# Board_Scale.net
KiCad netlist of a schematic drawn in Altium Designer
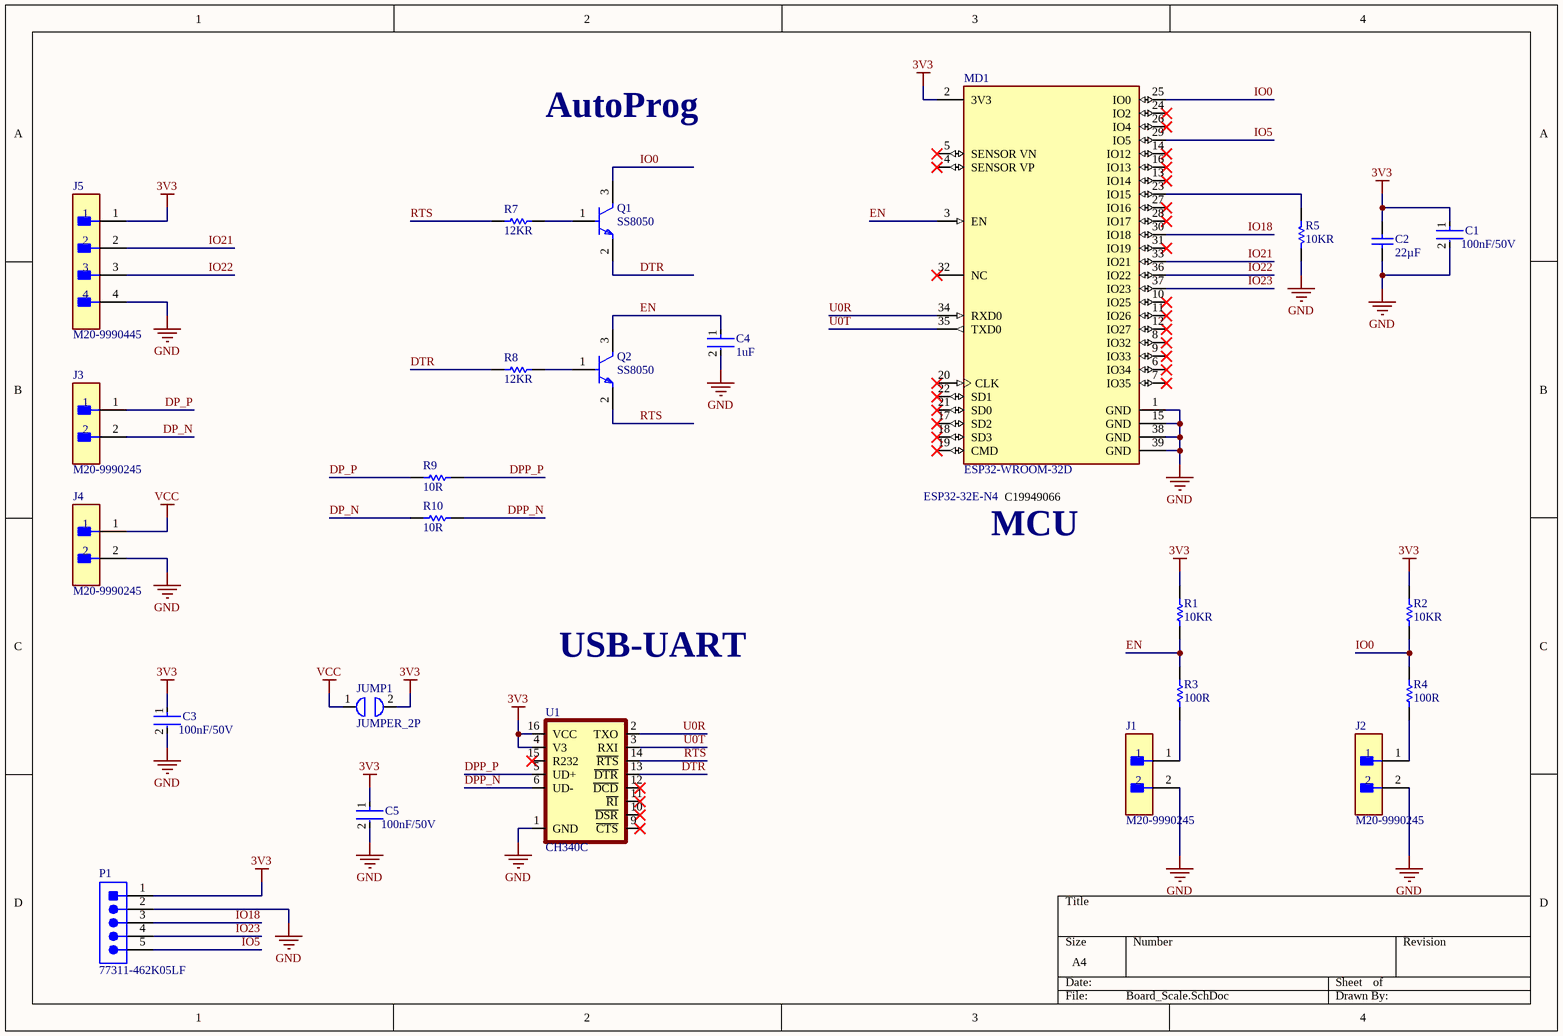
[diagram p0: Board_Scale.SchDoc]

(export (version "E")
  (design (tool "Eeschema 10.0.6"))
  (components
    (comp (ref "C1")
      (value "100nF/50V")
      (footprint "FP-CC0603-DA-MFG")
      (description "CAP CER 0.1UF 50V X7R 0603")
      (fields (field (name "MANUFACTURER") "YAGEO") (field (name "VOLTAGE") "50 V"))
      (libsource (lib "Altium Content Vault") (part "11868f565c42a9108669ba33697ecf6"))
    )
    (comp (ref "C2")
      (value "CL21A226MAQNNNE")
      (footprint "CAPC2013X140X45LL15T25")
      (description "Multi-layer Ceramic Capacitor, 22 uF, -55 to 85 degC, 2-Pin SMD (0805), RoHS, Tape and Reel")
      (fields
        (field (name "CAPACITANCE") "22µF")
        (field (name "MANUFACTURER") "Samsung Electro-Mechanics")
        (field (name "TOLERANCE") "±20%")
      )
      (libsource (lib "Altium Content Vault") (part "CAP-NP-2"))
    )
    (comp (ref "C3")
      (value "100nF/50V")
      (footprint "FP-CC0603-DA-MFG")
      (description "CAP CER 0.1UF 50V X7R 0603")
      (fields (field (name "MANUFACTURER") "YAGEO") (field (name "VOLTAGE") "50 V"))
      (libsource (lib "Altium Content Vault") (part "11868f565c42a9108669ba33697ecf6"))
    )
    (comp (ref "C4")
      (value "1uF")
      (footprint "FP-CL10-IPC_A")
      (description "Cap Ceramic 1uF 16V X5R ±10% Pad SMD 0603 +85°C T/R")
      (fields (field (name "TOLERANCE") "10%") (field (name "VOLTAGE") "16V"))
      (libsource (lib "Altium Content Vault") (part "b4654b650e69147ec39a6b967a45e02"))
    )
    (comp (ref "C5")
      (value "100nF/50V")
      (footprint "FP-CC0603-DA-MFG")
      (description "CAP CER 0.1UF 50V X7R 0603")
      (fields (field (name "MANUFACTURER") "YAGEO") (field (name "VOLTAGE") "50 V"))
      (libsource (lib "Altium Content Vault") (part "11868f565c42a9108669ba33697ecf6"))
    )
    (comp (ref "J1")
      (value "M20-9990245")
      (footprint "FP-M20-9990245-MFG")
      (description "CONN HEADER VERT 2POS 2.54MM")
      (fields (field (name "VOLTAGE") "50V"))
      (libsource (lib "Altium Content Vault") (part "3bc925449376181038e59eaffc5286c"))
    )
    (comp (ref "J2")
      (value "M20-9990245")
      (footprint "FP-M20-9990245-MFG")
      (description "CONN HEADER VERT 2POS 2.54MM")
      (fields (field (name "VOLTAGE") "50V"))
      (libsource (lib "Altium Content Vault") (part "3bc925449376181038e59eaffc5286c"))
    )
    (comp (ref "J3")
      (value "M20-9990245")
      (footprint "FP-M20-9990245-MFG")
      (description "CONN HEADER VERT 2POS 2.54MM")
      (fields (field (name "VOLTAGE") "50V"))
      (libsource (lib "Altium Content Vault") (part "3bc925449376181038e59eaffc5286c"))
    )
    (comp (ref "J4")
      (value "M20-9990245")
      (footprint "FP-M20-9990245-MFG")
      (description "CONN HEADER VERT 2POS 2.54MM")
      (fields (field (name "VOLTAGE") "50V"))
      (libsource (lib "Altium Content Vault") (part "3bc925449376181038e59eaffc5286c"))
    )
    (comp (ref "J5")
      (value "M20-9990445")
      (footprint "FP-M20-9990445-MFG")
      (description "M20-9990445 Conn Unshrouded Header HDR 4 POS 2.54mm Solder ST Thru-Hole Bulk/Loose")
      (libsource (lib "Altium Content Vault") (part "299a8cea1bdcbc3624fe62c390fa72c"))
    )
    (comp (ref "JUMP1")
      (value "JUMPER_2P")
      (footprint "JUMPER_2P")
      (libsource (lib "JUMPER_2P") (part "JUMPER_2P"))
    )
    (comp (ref "MD1")
      (value "ESP32-WROOM-32D")
      (footprint "FP-ESP32-WROOM-32D-MFG")
      (description "WIFI MODULE 32MBITS SPI FLASH")
      (fields
        (field (name "OCTOPART") "https://octopart.com/esp32-wroom-32d-espressif+systems-91040050")
        (field (name "MANUFACTURER") "Espressif Systems")
      )
      (libsource (lib "Altium Content Vault") (part "a031a76f8c27026a7a7f4657ff233a3"))
    )
    (comp (ref "P1")
      (value "77311-462K05LF")
      (footprint "FCI-77311-5_V")
      (libsource (lib "Altium Content Vault") (part "CN-1P-M-R5"))
    )
    (comp (ref "Q1")
      (value "SS8050")
      (footprint "FP-SS8050-G-MFG")
      (description "NPN TRANSISTOR 1.5A 40V SOT-23 R")
      (libsource (lib "Altium Content Vault") (part "2a1388f82443b098dcd57d24ac7632d"))
    )
    (comp (ref "Q2")
      (value "SS8050")
      (footprint "FP-SS8050-G-MFG")
      (description "NPN TRANSISTOR 1.5A 40V SOT-23 R")
      (libsource (lib "Altium Content Vault") (part "2a1388f82443b098dcd57d24ac7632d"))
    )
    (comp (ref "R1")
      (value "10KR")
      (footprint "RESC1609X55X30LL15T15")
      (description "Chip Resistor, 10 KOhm, +/- 1%, 0.1 W, -55 to 155 degC, 0603 (1608 Metric), RoHS, Tape and Reel")
      (fields (field (name "TOLERANCE") "1%") (field (name "MANUFACTURER") "Panasonic"))
      (libsource (lib "Altium Content Vault") (part "RES-2"))
    )
    (comp (ref "R2")
      (value "10KR")
      (footprint "RESC1609X55X30LL15T15")
      (description "Chip Resistor, 10 KOhm, +/- 1%, 0.1 W, -55 to 155 degC, 0603 (1608 Metric), RoHS, Tape and Reel")
      (fields (field (name "TOLERANCE") "1%") (field (name "MANUFACTURER") "Panasonic"))
      (libsource (lib "Altium Content Vault") (part "RES-2"))
    )
    (comp (ref "R3")
      (value "100R")
      (footprint "RESC1608X55X30LL15T15")
      (fields (field (name "MANUFACTURER") "Panasonic") (field (name "PART NUMBER") "ERJ-3EKF1000V"))
      (libsource (lib "Altium Content Vault") (part "RES"))
    )
    (comp (ref "R4")
      (value "100R")
      (footprint "RESC1608X55X30LL15T15")
      (fields (field (name "MANUFACTURER") "Panasonic") (field (name "PART NUMBER") "ERJ-3EKF1000V"))
      (libsource (lib "Altium Content Vault") (part "RES"))
    )
    (comp (ref "R5")
      (value "10KR")
      (footprint "RESC1609X55X30LL15T15")
      (description "Chip Resistor, 10 KOhm, +/- 1%, 0.1 W, -55 to 155 degC, 0603 (1608 Metric), RoHS, Tape and Reel")
      (fields (field (name "TOLERANCE") "1%") (field (name "MANUFACTURER") "Panasonic"))
      (libsource (lib "Altium Content Vault") (part "RES-2"))
    )
    (comp (ref "R7")
      (value "12KR")
      (footprint "RESC1608X55X25NL10T15")
      (description "Chip Resistor, 12 KOhm, +/- 1%, 100 mW, -55 to 155 degC, 0603 (1608 Metric), RoHS, Tape and Reel")
      (fields (field (name "TOLERANCE") "1%"))
      (libsource (lib "Altium Content Vault") (part "RES-2"))
    )
    (comp (ref "R8")
      (value "12KR")
      (footprint "RESC1608X55X25NL10T15")
      (description "Chip Resistor, 12 KOhm, +/- 1%, 100 mW, -55 to 155 degC, 0603 (1608 Metric), RoHS, Tape and Reel")
      (fields (field (name "TOLERANCE") "1%"))
      (libsource (lib "Altium Content Vault") (part "RES-2"))
    )
    (comp (ref "R9")
      (value "10R")
      (footprint "RESC1608X55X25NL10T15")
      (description "Chip Resistor, 10 Ohm, +/- 1%, 0.1 W, -55 to 155 degC, 0603 (1608 Metric), RoHS, Tape and Reel")
      (fields (field (name "MANUFACTURER") "Yageo"))
      (libsource (lib "Altium Content Vault") (part "RES-2"))
    )
    (comp (ref "R10")
      (value "10R")
      (footprint "RESC1608X55X25NL10T15")
      (description "Chip Resistor, 10 Ohm, +/- 1%, 0.1 W, -55 to 155 degC, 0603 (1608 Metric), RoHS, Tape and Reel")
      (fields (field (name "MANUFACTURER") "Yageo"))
      (libsource (lib "Altium Content Vault") (part "RES-2"))
    )
    (comp (ref "U1")
      (value "CH340C")
      (footprint "SO016")
      (description "Replacement for Brother P-Touch")
      (fields (field (name "MF") "Olimex"))
      (libsource (lib "CH340C") (part "CH340C"))
    )
  )
  (nets
    (net (code "1") (name "/DPP_N") (class "Default")
      (node (ref "R10") (pin "1") (pinfunction "1_1") (pintype "passive"))
      (node (ref "U1") (pin "6") (pinfunction "UD-_6") (pintype "bidirectional"))
    )
    (net (code "2") (name "/DPP_P") (class "Default")
      (node (ref "R9") (pin "1") (pinfunction "1_1") (pintype "passive"))
      (node (ref "U1") (pin "5") (pinfunction "UD+_5") (pintype "bidirectional"))
    )
    (net (code "3") (name "/DP_N") (class "Default")
      (node (ref "J3") (pin "2") (pinfunction "2_2") (pintype "passive"))
      (node (ref "R10") (pin "2") (pinfunction "2_2") (pintype "passive"))
    )
    (net (code "4") (name "/DP_P") (class "Default")
      (node (ref "J3") (pin "1") (pinfunction "1_1") (pintype "passive"))
      (node (ref "R9") (pin "2") (pinfunction "2_2") (pintype "passive"))
    )
    (net (code "5") (name "/DTR") (class "Default")
      (node (ref "Q1") (pin "2") (pinfunction "E_2") (pintype "passive"))
      (node (ref "R8") (pin "1") (pinfunction "1_1") (pintype "passive"))
      (node (ref "U1") (pin "13") (pinfunction "~{DTR}_13") (pintype "bidirectional"))
    )
    (net (code "6") (name "/EN") (class "Default")
      (node (ref "C4") (pin "1") (pinfunction "1_1") (pintype "passive"))
      (node (ref "MD1") (pin "3") (pinfunction "EN_3") (pintype "input"))
      (node (ref "Q2") (pin "3") (pinfunction "C_3") (pintype "passive"))
      (node (ref "R1") (pin "2") (pinfunction "2_2") (pintype "passive"))
      (node (ref "R3") (pin "2") (pinfunction "2_2") (pintype "passive"))
    )
    (net (code "7") (name "/IO0") (class "Default")
      (node (ref "MD1") (pin "25") (pinfunction "IO0_25") (pintype "bidirectional"))
      (node (ref "Q1") (pin "3") (pinfunction "C_3") (pintype "passive"))
      (node (ref "R2") (pin "2") (pinfunction "2_2") (pintype "passive"))
      (node (ref "R4") (pin "2") (pinfunction "2_2") (pintype "passive"))
    )
    (net (code "8") (name "/IO5") (class "Default")
      (node (ref "MD1") (pin "29") (pinfunction "IO5_29") (pintype "bidirectional"))
      (node (ref "P1") (pin "5") (pinfunction "CTS_5") (pintype "passive"))
    )
    (net (code "9") (name "/IO18") (class "Default")
      (node (ref "MD1") (pin "30") (pinfunction "IO18_30") (pintype "bidirectional"))
      (node (ref "P1") (pin "3") (pinfunction "TXO_3") (pintype "passive"))
    )
    (net (code "10") (name "/IO21") (class "Default")
      (node (ref "J5") (pin "2") (pinfunction "2_2") (pintype "passive"))
      (node (ref "MD1") (pin "33") (pinfunction "IO21_33") (pintype "bidirectional"))
    )
    (net (code "11") (name "/IO22") (class "Default")
      (node (ref "J5") (pin "3") (pinfunction "3_3") (pintype "passive"))
      (node (ref "MD1") (pin "36") (pinfunction "IO22_36") (pintype "bidirectional"))
    )
    (net (code "12") (name "/IO23") (class "Default")
      (node (ref "MD1") (pin "37") (pinfunction "IO23_37") (pintype "bidirectional"))
      (node (ref "P1") (pin "4") (pinfunction "VCC_4") (pintype "passive"))
    )
    (net (code "13") (name "/RTS") (class "Default")
      (node (ref "Q2") (pin "2") (pinfunction "E_2") (pintype "passive"))
      (node (ref "R7") (pin "1") (pinfunction "1_1") (pintype "passive"))
      (node (ref "U1") (pin "14") (pinfunction "~{RTS}_14") (pintype "bidirectional"))
    )
    (net (code "14") (name "/U0R") (class "Default")
      (node (ref "MD1") (pin "34") (pinfunction "RXD0_34") (pintype "input"))
      (node (ref "U1") (pin "2") (pinfunction "TXO_2") (pintype "bidirectional"))
    )
    (net (code "15") (name "/U0T") (class "Default")
      (node (ref "MD1") (pin "35") (pinfunction "TXD0_35") (pintype "output"))
      (node (ref "U1") (pin "3") (pinfunction "RXI_3") (pintype "bidirectional"))
    )
    (net (code "16") (name "3V3") (class "Default")
      (node (ref "C1") (pin "1") (pinfunction "1_1") (pintype "passive"))
      (node (ref "C2") (pin "2") (pinfunction "2_2") (pintype "passive"))
      (node (ref "C3") (pin "1") (pinfunction "1_1") (pintype "passive"))
      (node (ref "C5") (pin "1") (pinfunction "1_1") (pintype "passive"))
      (node (ref "J5") (pin "1") (pinfunction "1_1") (pintype "passive"))
      (node (ref "JUMP1") (pin "2") (pinfunction "2_2") (pintype "passive"))
      (node (ref "MD1") (pin "2") (pinfunction "3V3_2") (pintype "power_in"))
      (node (ref "P1") (pin "1") (pinfunction "DTR_1") (pintype "passive"))
      (node (ref "R1") (pin "1") (pinfunction "1_1") (pintype "passive"))
      (node (ref "R2") (pin "1") (pinfunction "1_1") (pintype "passive"))
      (node (ref "U1") (pin "16") (pinfunction "VCC_16") (pintype "bidirectional"))
      (node (ref "U1") (pin "4") (pinfunction "V3_4") (pintype "bidirectional"))
    )
    (net (code "17") (name "GND") (class "Default")
      (node (ref "C1") (pin "2") (pinfunction "2_2") (pintype "passive"))
      (node (ref "C2") (pin "1") (pinfunction "1_1") (pintype "passive"))
      (node (ref "C3") (pin "2") (pinfunction "2_2") (pintype "passive"))
      (node (ref "C4") (pin "2") (pinfunction "2_2") (pintype "passive"))
      (node (ref "C5") (pin "2") (pinfunction "2_2") (pintype "passive"))
      (node (ref "J1") (pin "2") (pinfunction "2_2") (pintype "passive"))
      (node (ref "J2") (pin "2") (pinfunction "2_2") (pintype "passive"))
      (node (ref "J4") (pin "2") (pinfunction "2_2") (pintype "passive"))
      (node (ref "J5") (pin "4") (pinfunction "4_4") (pintype "passive"))
      (node (ref "MD1") (pin "1") (pinfunction "GND_1") (pintype "power_in"))
      (node (ref "MD1") (pin "15") (pinfunction "GND_15") (pintype "power_in"))
      (node (ref "MD1") (pin "38") (pinfunction "GND_38") (pintype "power_in"))
      (node (ref "MD1") (pin "39") (pinfunction "GND_39") (pintype "power_in"))
      (node (ref "P1") (pin "2") (pinfunction "RXI_2") (pintype "passive"))
      (node (ref "R5") (pin "2") (pinfunction "2_2") (pintype "passive"))
      (node (ref "U1") (pin "1") (pinfunction "GND_1") (pintype "bidirectional"))
    )
    (net (code "18") (name "Net-(J1-Pad1)") (class "Default")
      (node (ref "J1") (pin "1") (pinfunction "1_1") (pintype "passive"))
      (node (ref "R3") (pin "1") (pinfunction "1_1") (pintype "passive"))
    )
    (net (code "19") (name "Net-(J2-Pad1)") (class "Default")
      (node (ref "J2") (pin "1") (pinfunction "1_1") (pintype "passive"))
      (node (ref "R4") (pin "1") (pinfunction "1_1") (pintype "passive"))
    )
    (net (code "20") (name "Net-(MD1-IO15)") (class "Default")
      (node (ref "MD1") (pin "23") (pinfunction "IO15_23") (pintype "bidirectional"))
      (node (ref "R5") (pin "1") (pinfunction "1_1") (pintype "passive"))
    )
    (net (code "21") (name "Net-(Q1-B)") (class "Default")
      (node (ref "Q1") (pin "1") (pinfunction "B_1") (pintype "passive"))
      (node (ref "R7") (pin "2") (pinfunction "2_2") (pintype "passive"))
    )
    (net (code "22") (name "Net-(Q2-B)") (class "Default")
      (node (ref "Q2") (pin "1") (pinfunction "B_1") (pintype "passive"))
      (node (ref "R8") (pin "2") (pinfunction "2_2") (pintype "passive"))
    )
    (net (code "23") (name "VCC") (class "Default")
      (node (ref "J4") (pin "1") (pinfunction "1_1") (pintype "passive"))
      (node (ref "JUMP1") (pin "1") (pinfunction "1_1") (pintype "passive"))
    )
    (net (code "24") (name "unconnected-(MD1-CLK-Pad20)") (class "Default")
      (node (ref "MD1") (pin "20") (pinfunction "CLK_20") (pintype "input+no_connect"))
    )
    (net (code "25") (name "unconnected-(MD1-CMD-Pad19)") (class "Default")
      (node (ref "MD1") (pin "19") (pinfunction "CMD_19") (pintype "bidirectional+no_connect"))
    )
    (net (code "26") (name "unconnected-(MD1-IO2-Pad24)") (class "Default")
      (node (ref "MD1") (pin "24") (pinfunction "IO2_24") (pintype "bidirectional+no_connect"))
    )
    (net (code "27") (name "unconnected-(MD1-IO4-Pad26)") (class "Default")
      (node (ref "MD1") (pin "26") (pinfunction "IO4_26") (pintype "bidirectional+no_connect"))
    )
    (net (code "28") (name "unconnected-(MD1-IO12-Pad14)") (class "Default")
      (node (ref "MD1") (pin "14") (pinfunction "IO12_14") (pintype "bidirectional+no_connect"))
    )
    (net (code "29") (name "unconnected-(MD1-IO13-Pad16)") (class "Default")
      (node (ref "MD1") (pin "16") (pinfunction "IO13_16") (pintype "bidirectional+no_connect"))
    )
    (net (code "30") (name "unconnected-(MD1-IO14-Pad13)") (class "Default")
      (node (ref "MD1") (pin "13") (pinfunction "IO14_13") (pintype "bidirectional+no_connect"))
    )
    (net (code "31") (name "unconnected-(MD1-IO16-Pad27)") (class "Default")
      (node (ref "MD1") (pin "27") (pinfunction "IO16_27") (pintype "bidirectional+no_connect"))
    )
    (net (code "32") (name "unconnected-(MD1-IO17-Pad28)") (class "Default")
      (node (ref "MD1") (pin "28") (pinfunction "IO17_28") (pintype "bidirectional+no_connect"))
    )
    (net (code "33") (name "unconnected-(MD1-IO19-Pad31)") (class "Default")
      (node (ref "MD1") (pin "31") (pinfunction "IO19_31") (pintype "bidirectional+no_connect"))
    )
    (net (code "34") (name "unconnected-(MD1-IO25-Pad10)") (class "Default")
      (node (ref "MD1") (pin "10") (pinfunction "IO25_10") (pintype "bidirectional+no_connect"))
    )
    (net (code "35") (name "unconnected-(MD1-IO26-Pad11)") (class "Default")
      (node (ref "MD1") (pin "11") (pinfunction "IO26_11") (pintype "bidirectional+no_connect"))
    )
    (net (code "36") (name "unconnected-(MD1-IO27-Pad12)") (class "Default")
      (node (ref "MD1") (pin "12") (pinfunction "IO27_12") (pintype "bidirectional+no_connect"))
    )
    (net (code "37") (name "unconnected-(MD1-IO32-Pad8)") (class "Default")
      (node (ref "MD1") (pin "8") (pinfunction "IO32_8") (pintype "bidirectional+no_connect"))
    )
    (net (code "38") (name "unconnected-(MD1-IO33-Pad9)") (class "Default")
      (node (ref "MD1") (pin "9") (pinfunction "IO33_9") (pintype "bidirectional+no_connect"))
    )
    (net (code "39") (name "unconnected-(MD1-IO34-Pad6)") (class "Default")
      (node (ref "MD1") (pin "6") (pinfunction "IO34_6") (pintype "bidirectional+no_connect"))
    )
    (net (code "40") (name "unconnected-(MD1-IO35-Pad7)") (class "Default")
      (node (ref "MD1") (pin "7") (pinfunction "IO35_7") (pintype "bidirectional+no_connect"))
    )
    (net (code "41") (name "unconnected-(MD1-NC-Pad32)") (class "Default")
      (node (ref "MD1") (pin "32") (pinfunction "NC_32") (pintype "passive+no_connect"))
    )
    (net (code "42") (name "unconnected-(MD1-SD0-Pad21)") (class "Default")
      (node (ref "MD1") (pin "21") (pinfunction "SD0_21") (pintype "bidirectional+no_connect"))
    )
    (net (code "43") (name "unconnected-(MD1-SD1-Pad22)") (class "Default")
      (node (ref "MD1") (pin "22") (pinfunction "SD1_22") (pintype "bidirectional+no_connect"))
    )
    (net (code "44") (name "unconnected-(MD1-SD2-Pad17)") (class "Default")
      (node (ref "MD1") (pin "17") (pinfunction "SD2_17") (pintype "bidirectional+no_connect"))
    )
    (net (code "45") (name "unconnected-(MD1-SD3-Pad18)") (class "Default")
      (node (ref "MD1") (pin "18") (pinfunction "SD3_18") (pintype "bidirectional+no_connect"))
    )
    (net (code "46") (name "unconnected-(MD1-SENSOR_VN-Pad5)") (class "Default")
      (node (ref "MD1") (pin "5") (pinfunction "SENSOR_VN_5") (pintype "bidirectional+no_connect"))
    )
    (net (code "47") (name "unconnected-(MD1-SENSOR_VP-Pad4)") (class "Default")
      (node (ref "MD1") (pin "4") (pinfunction "SENSOR_VP_4") (pintype "bidirectional+no_connect"))
    )
    (net (code "48") (name "unconnected-(U1-R232-Pad15)") (class "Default")
      (node (ref "U1") (pin "15") (pinfunction "R232_15") (pintype "bidirectional+no_connect"))
    )
    (net (code "49") (name "unconnected-(U1-~{CTS}-Pad9)") (class "Default")
      (node (ref "U1") (pin "9") (pinfunction "~{CTS}_9") (pintype "bidirectional+no_connect"))
    )
    (net (code "50") (name "unconnected-(U1-~{DCD}-Pad12)") (class "Default")
      (node (ref "U1") (pin "12") (pinfunction "~{DCD}_12") (pintype "bidirectional+no_connect"))
    )
    (net (code "51") (name "unconnected-(U1-~{DSR}-Pad10)") (class "Default")
      (node (ref "U1") (pin "10") (pinfunction "~{DSR}_10") (pintype "bidirectional+no_connect"))
    )
    (net (code "52") (name "unconnected-(U1-~{RI}-Pad11)") (class "Default")
      (node (ref "U1") (pin "11") (pinfunction "~{RI}_11") (pintype "bidirectional+no_connect"))
    )
  )
)
